# counter.net
KiCad netlist of a schematic drawn in EAGLE
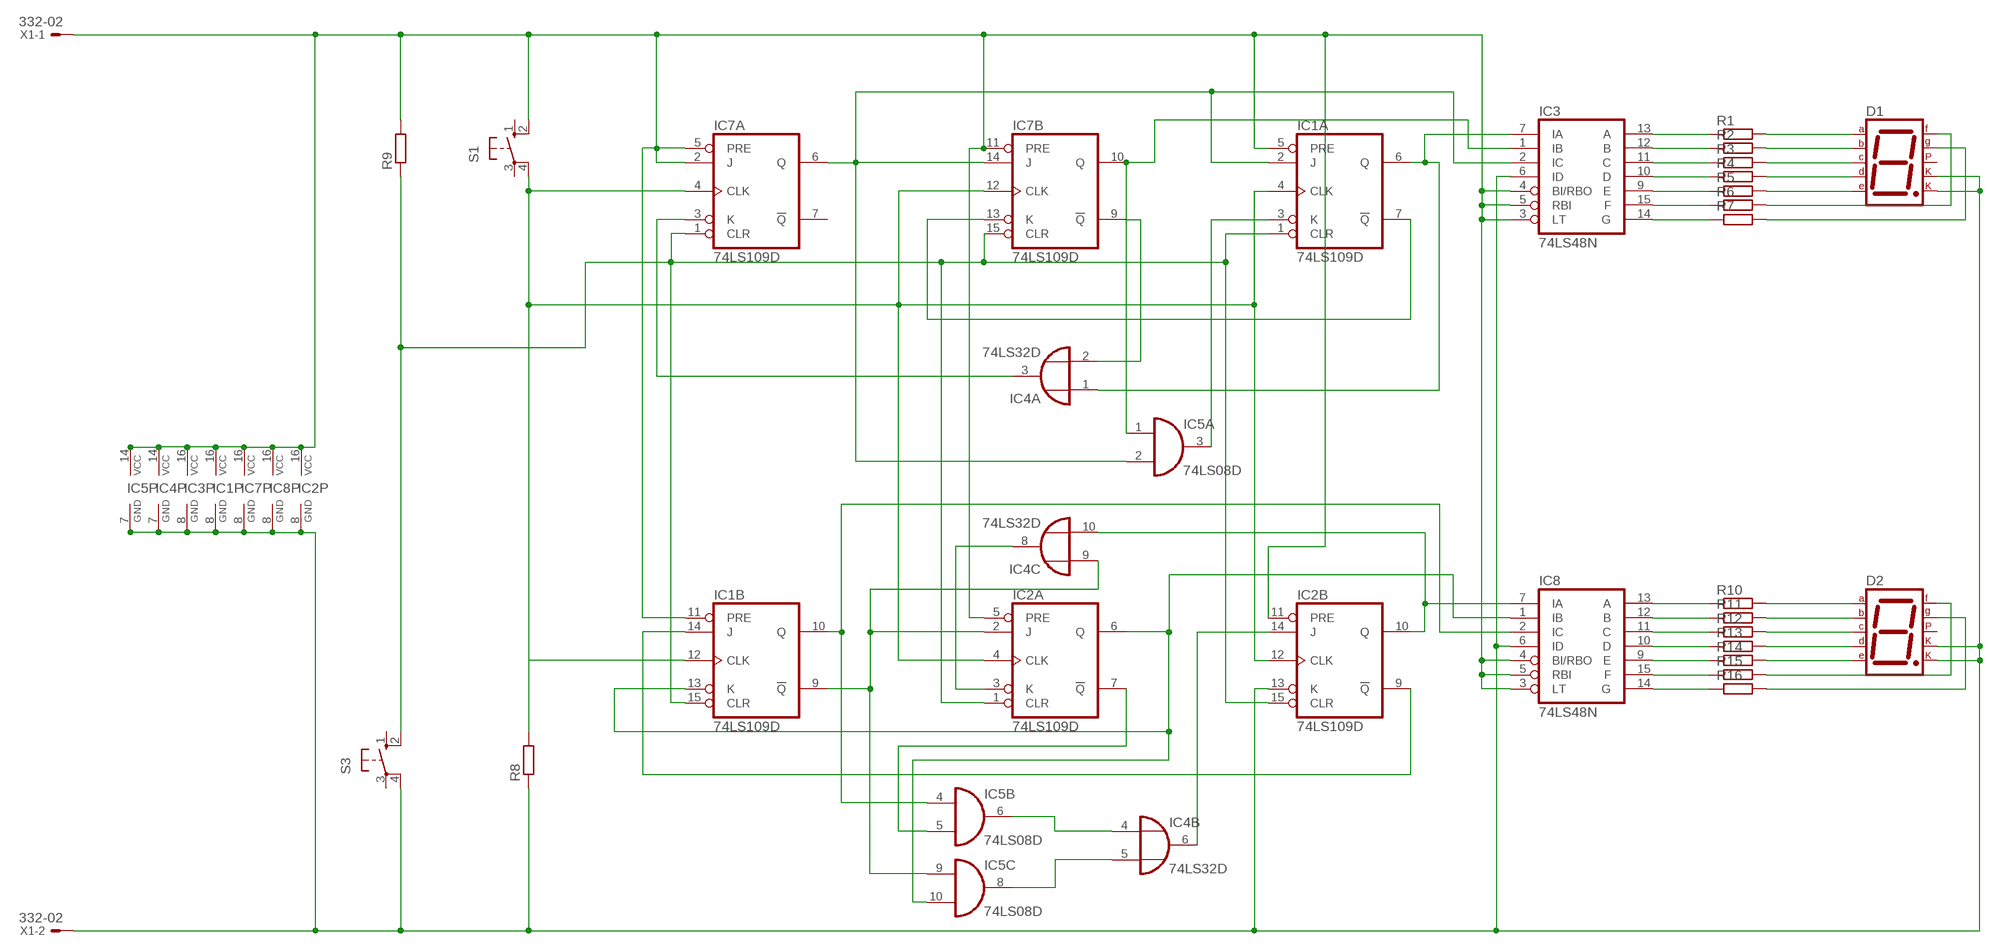
[diagram p0: schematic, sheet 1]

(export (version "E")
  (design (tool "Eeschema 10.0.6"))
  (components
    (comp (ref "D1")
      (value "7SEG-CK")
      (footprint "eagle-import:7SEG-13")
      (libsource (lib "eagle-import") (part "7SEG-CK"))
    )
    (comp (ref "D2")
      (value "7SEG-CK")
      (footprint "eagle-import:7SEG-13")
      (libsource (lib "eagle-import") (part "7SEG-CK"))
    )
    (comp (ref "IC1")
      (value "74LS109D")
      (footprint "eagle-import:SO16")
      (libsource (lib "eagle-import") (part "74109DLS"))
    )
    (comp (ref "IC2")
      (value "74LS109D")
      (footprint "eagle-import:SO16")
      (libsource (lib "eagle-import") (part "74109DLS"))
    )
    (comp (ref "IC3")
      (value "74LS48N")
      (footprint "eagle-import:DIL16")
      (libsource (lib "eagle-import") (part "7448NLS"))
    )
    (comp (ref "IC4")
      (value "74LS32D")
      (footprint "eagle-import:SO14")
      (libsource (lib "eagle-import") (part "7432DLS"))
    )
    (comp (ref "IC5")
      (value "74LS08D")
      (footprint "eagle-import:SO14")
      (libsource (lib "eagle-import") (part "7408DLS"))
    )
    (comp (ref "IC7")
      (value "74LS109D")
      (footprint "eagle-import:SO16")
      (libsource (lib "eagle-import") (part "74109DLS"))
    )
    (comp (ref "IC8")
      (value "74LS48N")
      (footprint "eagle-import:DIL16")
      (libsource (lib "eagle-import") (part "7448NLS"))
    )
    (comp (ref "R1")
      (value "R-EU_M0805")
      (footprint "eagle-import:M0805")
      (libsource (lib "eagle-import") (part "R-EU_M0805"))
    )
    (comp (ref "R2")
      (value "R-EU_M0805")
      (footprint "eagle-import:M0805")
      (libsource (lib "eagle-import") (part "R-EU_M0805"))
    )
    (comp (ref "R3")
      (value "R-EU_M0805")
      (footprint "eagle-import:M0805")
      (libsource (lib "eagle-import") (part "R-EU_M0805"))
    )
    (comp (ref "R4")
      (value "R-EU_M0805")
      (footprint "eagle-import:M0805")
      (libsource (lib "eagle-import") (part "R-EU_M0805"))
    )
    (comp (ref "R5")
      (value "R-EU_M0805")
      (footprint "eagle-import:M0805")
      (libsource (lib "eagle-import") (part "R-EU_M0805"))
    )
    (comp (ref "R6")
      (value "R-EU_M0805")
      (footprint "eagle-import:M0805")
      (libsource (lib "eagle-import") (part "R-EU_M0805"))
    )
    (comp (ref "R7")
      (value "R-EU_M0805")
      (footprint "eagle-import:M0805")
      (libsource (lib "eagle-import") (part "R-EU_M0805"))
    )
    (comp (ref "R8")
      (value "R-EU_M0805")
      (footprint "eagle-import:M0805")
      (libsource (lib "eagle-import") (part "R-EU_M0805"))
    )
    (comp (ref "R9")
      (value "R-EU_M0805")
      (footprint "eagle-import:M0805")
      (libsource (lib "eagle-import") (part "R-EU_M0805"))
    )
    (comp (ref "R10")
      (value "R-EU_M0805")
      (footprint "eagle-import:M0805")
      (libsource (lib "eagle-import") (part "R-EU_M0805"))
    )
    (comp (ref "R11")
      (value "R-EU_M0805")
      (footprint "eagle-import:M0805")
      (libsource (lib "eagle-import") (part "R-EU_M0805"))
    )
    (comp (ref "R12")
      (value "R-EU_M0805")
      (footprint "eagle-import:M0805")
      (libsource (lib "eagle-import") (part "R-EU_M0805"))
    )
    (comp (ref "R13")
      (value "R-EU_M0805")
      (footprint "eagle-import:M0805")
      (libsource (lib "eagle-import") (part "R-EU_M0805"))
    )
    (comp (ref "R14")
      (value "R-EU_M0805")
      (footprint "eagle-import:M0805")
      (libsource (lib "eagle-import") (part "R-EU_M0805"))
    )
    (comp (ref "R15")
      (value "R-EU_M0805")
      (footprint "eagle-import:M0805")
      (libsource (lib "eagle-import") (part "R-EU_M0805"))
    )
    (comp (ref "R16")
      (value "R-EU_M0805")
      (footprint "eagle-import:M0805")
      (libsource (lib "eagle-import") (part "R-EU_M0805"))
    )
    (comp (ref "S1")
      (value "10-XX")
      (footprint "eagle-import:B3F-10XX")
      (fields (field (name "MPN") "B3F-1000"))
      (libsource (lib "eagle-import") (part "10-XX"))
    )
    (comp (ref "S3")
      (value "10-XX")
      (footprint "eagle-import:B3F-10XX")
      (fields (field (name "MPN") "B3F-1000"))
      (libsource (lib "eagle-import") (part "10-XX"))
    )
    (comp (ref "X1")
      (value "332-02")
      (footprint "eagle-import:332-02")
      (libsource (lib "eagle-import") (part "332-02"))
    )
  )
  (nets
    (net (code "1") (name "Net-(D1-A)") (class "Default")
      (node (ref "D1") (pin "7") (pinfunction "A_7") (pintype "passive"))
      (node (ref "R1") (pin "2") (pinfunction "2_2") (pintype "passive"))
    )
    (net (code "2") (name "Net-(D1-B)") (class "Default")
      (node (ref "D1") (pin "6") (pinfunction "B_6") (pintype "passive"))
      (node (ref "R2") (pin "2") (pinfunction "2_2") (pintype "passive"))
    )
    (net (code "3") (name "Net-(D1-C)") (class "Default")
      (node (ref "D1") (pin "4") (pinfunction "C_4") (pintype "passive"))
      (node (ref "R3") (pin "2") (pinfunction "2_2") (pintype "passive"))
    )
    (net (code "4") (name "Net-(D1-CK1)") (class "Default")
      (node (ref "D1") (pin "3") (pinfunction "CK1_3") (pintype "passive"))
      (node (ref "D1") (pin "8") (pinfunction "CK2_8") (pintype "passive"))
      (node (ref "D2") (pin "3") (pinfunction "CK1_3") (pintype "passive"))
      (node (ref "D2") (pin "8") (pinfunction "CK2_8") (pintype "passive"))
      (node (ref "IC1") (pin "8") (pinfunction "GND_8") (pintype "power_in"))
      (node (ref "IC2") (pin "13") (pinfunction "K_13") (pintype "input"))
      (node (ref "IC2") (pin "8") (pinfunction "GND_8") (pintype "power_in"))
      (node (ref "IC3") (pin "6") (pinfunction "ID_6") (pintype "input"))
      (node (ref "IC3") (pin "8") (pinfunction "GND_8") (pintype "power_in"))
      (node (ref "IC4") (pin "7") (pinfunction "GND_7") (pintype "power_in"))
      (node (ref "IC5") (pin "7") (pinfunction "GND_7") (pintype "power_in"))
      (node (ref "IC7") (pin "8") (pinfunction "GND_8") (pintype "power_in"))
      (node (ref "IC8") (pin "6") (pinfunction "ID_6") (pintype "input"))
      (node (ref "IC8") (pin "8") (pinfunction "GND_8") (pintype "power_in"))
      (node (ref "R8") (pin "1") (pinfunction "1_1") (pintype "passive"))
      (node (ref "S3") (pin "4") (pinfunction "P1_4") (pintype "passive"))
      (node (ref "X1") (pin "2") (pinfunction "S_2") (pintype "passive"))
    )
    (net (code "5") (name "Net-(D1-D)") (class "Default")
      (node (ref "D1") (pin "2") (pinfunction "D_2") (pintype "passive"))
      (node (ref "R4") (pin "2") (pinfunction "2_2") (pintype "passive"))
    )
    (net (code "6") (name "Net-(D1-E)") (class "Default")
      (node (ref "D1") (pin "1") (pinfunction "E_1") (pintype "passive"))
      (node (ref "R5") (pin "2") (pinfunction "2_2") (pintype "passive"))
    )
    (net (code "7") (name "Net-(D1-F)") (class "Default")
      (node (ref "D1") (pin "9") (pinfunction "F_9") (pintype "passive"))
      (node (ref "R6") (pin "2") (pinfunction "2_2") (pintype "passive"))
    )
    (net (code "8") (name "Net-(D1-G)") (class "Default")
      (node (ref "D1") (pin "10") (pinfunction "G_10") (pintype "passive"))
      (node (ref "R7") (pin "2") (pinfunction "2_2") (pintype "passive"))
    )
    (net (code "9") (name "Net-(D2-A)") (class "Default")
      (node (ref "D2") (pin "7") (pinfunction "A_7") (pintype "passive"))
      (node (ref "R10") (pin "2") (pinfunction "2_2") (pintype "passive"))
    )
    (net (code "10") (name "Net-(D2-B)") (class "Default")
      (node (ref "D2") (pin "6") (pinfunction "B_6") (pintype "passive"))
      (node (ref "R11") (pin "2") (pinfunction "2_2") (pintype "passive"))
    )
    (net (code "11") (name "Net-(D2-C)") (class "Default")
      (node (ref "D2") (pin "4") (pinfunction "C_4") (pintype "passive"))
      (node (ref "R12") (pin "2") (pinfunction "2_2") (pintype "passive"))
    )
    (net (code "12") (name "Net-(D2-D)") (class "Default")
      (node (ref "D2") (pin "2") (pinfunction "D_2") (pintype "passive"))
      (node (ref "R13") (pin "2") (pinfunction "2_2") (pintype "passive"))
    )
    (net (code "13") (name "Net-(D2-E)") (class "Default")
      (node (ref "D2") (pin "1") (pinfunction "E_1") (pintype "passive"))
      (node (ref "R14") (pin "2") (pinfunction "2_2") (pintype "passive"))
    )
    (net (code "14") (name "Net-(D2-F)") (class "Default")
      (node (ref "D2") (pin "9") (pinfunction "F_9") (pintype "passive"))
      (node (ref "R15") (pin "2") (pinfunction "2_2") (pintype "passive"))
    )
    (net (code "15") (name "Net-(D2-G)") (class "Default")
      (node (ref "D2") (pin "10") (pinfunction "G_10") (pintype "passive"))
      (node (ref "R16") (pin "2") (pinfunction "2_2") (pintype "passive"))
    )
    (net (code "16") (name "Net-(IC1A-CLK)") (class "Default")
      (node (ref "IC1") (pin "12") (pinfunction "CLK_12") (pintype "input"))
      (node (ref "IC1") (pin "4") (pinfunction "CLK_4") (pintype "input"))
      (node (ref "IC2") (pin "12") (pinfunction "CLK_12") (pintype "input"))
      (node (ref "IC2") (pin "4") (pinfunction "CLK_4") (pintype "input"))
      (node (ref "IC7") (pin "12") (pinfunction "CLK_12") (pintype "input"))
      (node (ref "IC7") (pin "4") (pinfunction "CLK_4") (pintype "input"))
      (node (ref "R8") (pin "2") (pinfunction "2_2") (pintype "passive"))
      (node (ref "S1") (pin "4") (pinfunction "P1_4") (pintype "passive"))
    )
    (net (code "17") (name "Net-(IC1A-CLR)") (class "Default")
      (node (ref "IC1") (pin "1") (pinfunction "CLR_1") (pintype "input"))
      (node (ref "IC1") (pin "15") (pinfunction "CLR_15") (pintype "input"))
      (node (ref "IC2") (pin "1") (pinfunction "CLR_1") (pintype "input"))
      (node (ref "IC2") (pin "15") (pinfunction "CLR_15") (pintype "input"))
      (node (ref "IC7") (pin "1") (pinfunction "CLR_1") (pintype "input"))
      (node (ref "IC7") (pin "15") (pinfunction "CLR_15") (pintype "input"))
      (node (ref "R9") (pin "1") (pinfunction "1_1") (pintype "passive"))
      (node (ref "S3") (pin "2") (pinfunction "S1_2") (pintype "passive"))
    )
    (net (code "18") (name "Net-(IC1A-J)") (class "Default")
      (node (ref "IC1") (pin "2") (pinfunction "J_2") (pintype "input"))
      (node (ref "IC3") (pin "2") (pinfunction "IC_2") (pintype "input"))
      (node (ref "IC5") (pin "2") (pinfunction "I1_2") (pintype "input"))
      (node (ref "IC7") (pin "14") (pinfunction "J_14") (pintype "input"))
      (node (ref "IC7") (pin "6") (pinfunction "Q_6") (pintype "output"))
    )
    (net (code "19") (name "Net-(IC1A-K)") (class "Default")
      (node (ref "IC1") (pin "3") (pinfunction "K_3") (pintype "input"))
      (node (ref "IC5") (pin "3") (pinfunction "O_3") (pintype "output"))
    )
    (net (code "20") (name "Net-(IC1A-PRE)") (class "Default")
      (node (ref "IC1") (pin "11") (pinfunction "PRE_11") (pintype "input"))
      (node (ref "IC1") (pin "16") (pinfunction "VCC_16") (pintype "power_in"))
      (node (ref "IC1") (pin "5") (pinfunction "PRE_5") (pintype "input"))
      (node (ref "IC2") (pin "11") (pinfunction "PRE_11") (pintype "input"))
      (node (ref "IC2") (pin "16") (pinfunction "VCC_16") (pintype "power_in"))
      (node (ref "IC2") (pin "5") (pinfunction "PRE_5") (pintype "input"))
      (node (ref "IC3") (pin "16") (pinfunction "VCC_16") (pintype "power_in"))
      (node (ref "IC3") (pin "3") (pinfunction "LT_3") (pintype "input"))
      (node (ref "IC3") (pin "4") (pinfunction "BI/RBO_4") (pintype "input"))
      (node (ref "IC3") (pin "5") (pinfunction "RBI_5") (pintype "input"))
      (node (ref "IC4") (pin "14") (pinfunction "VCC_14") (pintype "power_in"))
      (node (ref "IC5") (pin "14") (pinfunction "VCC_14") (pintype "power_in"))
      (node (ref "IC7") (pin "11") (pinfunction "PRE_11") (pintype "input"))
      (node (ref "IC7") (pin "16") (pinfunction "VCC_16") (pintype "power_in"))
      (node (ref "IC7") (pin "2") (pinfunction "J_2") (pintype "input"))
      (node (ref "IC7") (pin "5") (pinfunction "PRE_5") (pintype "input"))
      (node (ref "IC8") (pin "16") (pinfunction "VCC_16") (pintype "power_in"))
      (node (ref "IC8") (pin "3") (pinfunction "LT_3") (pintype "input"))
      (node (ref "IC8") (pin "4") (pinfunction "BI/RBO_4") (pintype "input"))
      (node (ref "IC8") (pin "5") (pinfunction "RBI_5") (pintype "input"))
      (node (ref "R9") (pin "2") (pinfunction "2_2") (pintype "passive"))
      (node (ref "S1") (pin "2") (pinfunction "S1_2") (pintype "passive"))
      (node (ref "X1") (pin "1") (pinfunction "S_1") (pintype "passive"))
    )
    (net (code "21") (name "Net-(IC1A-Q)") (class "Default")
      (node (ref "IC1") (pin "6") (pinfunction "Q_6") (pintype "output"))
      (node (ref "IC3") (pin "7") (pinfunction "IA_7") (pintype "input"))
      (node (ref "IC4") (pin "1") (pinfunction "I0_1") (pintype "input"))
    )
    (net (code "22") (name "Net-(IC1A-~{Q})") (class "Default")
      (node (ref "IC1") (pin "7") (pinfunction "~{Q}_7") (pintype "output"))
      (node (ref "IC7") (pin "13") (pinfunction "K_13") (pintype "input"))
    )
    (net (code "23") (name "Net-(IC1B-J)") (class "Default")
      (node (ref "IC1") (pin "14") (pinfunction "J_14") (pintype "input"))
      (node (ref "IC2") (pin "9") (pinfunction "~{Q}_9") (pintype "output"))
    )
    (net (code "24") (name "Net-(IC1B-K)") (class "Default")
      (node (ref "IC1") (pin "13") (pinfunction "K_13") (pintype "input"))
      (node (ref "IC2") (pin "6") (pinfunction "Q_6") (pintype "output"))
      (node (ref "IC5") (pin "10") (pinfunction "I1_10") (pintype "input"))
      (node (ref "IC8") (pin "1") (pinfunction "IB_1") (pintype "input"))
    )
    (net (code "25") (name "Net-(IC1B-Q)") (class "Default")
      (node (ref "IC1") (pin "10") (pinfunction "Q_10") (pintype "output"))
      (node (ref "IC5") (pin "4") (pinfunction "I0_4") (pintype "input"))
      (node (ref "IC8") (pin "2") (pinfunction "IC_2") (pintype "input"))
    )
    (net (code "26") (name "Net-(IC1B-~{Q})") (class "Default")
      (node (ref "IC1") (pin "9") (pinfunction "~{Q}_9") (pintype "output"))
      (node (ref "IC2") (pin "2") (pinfunction "J_2") (pintype "input"))
      (node (ref "IC4") (pin "9") (pinfunction "I0_9") (pintype "input"))
      (node (ref "IC5") (pin "9") (pinfunction "I0_9") (pintype "input"))
    )
    (net (code "27") (name "Net-(IC2A-K)") (class "Default")
      (node (ref "IC2") (pin "3") (pinfunction "K_3") (pintype "input"))
      (node (ref "IC4") (pin "8") (pinfunction "O_8") (pintype "output"))
    )
    (net (code "28") (name "Net-(IC2A-~{Q})") (class "Default")
      (node (ref "IC2") (pin "7") (pinfunction "~{Q}_7") (pintype "output"))
      (node (ref "IC5") (pin "5") (pinfunction "I1_5") (pintype "input"))
    )
    (net (code "29") (name "Net-(IC2B-J)") (class "Default")
      (node (ref "IC2") (pin "14") (pinfunction "J_14") (pintype "input"))
      (node (ref "IC4") (pin "6") (pinfunction "O_6") (pintype "output"))
    )
    (net (code "30") (name "Net-(IC2B-Q)") (class "Default")
      (node (ref "IC2") (pin "10") (pinfunction "Q_10") (pintype "output"))
      (node (ref "IC4") (pin "10") (pinfunction "I1_10") (pintype "input"))
      (node (ref "IC8") (pin "7") (pinfunction "IA_7") (pintype "input"))
    )
    (net (code "31") (name "Net-(IC3A-A)") (class "Default")
      (node (ref "IC3") (pin "13") (pinfunction "A_13") (pintype "output"))
      (node (ref "R1") (pin "1") (pinfunction "1_1") (pintype "passive"))
    )
    (net (code "32") (name "Net-(IC3A-B)") (class "Default")
      (node (ref "IC3") (pin "12") (pinfunction "B_12") (pintype "output"))
      (node (ref "R2") (pin "1") (pinfunction "1_1") (pintype "passive"))
    )
    (net (code "33") (name "Net-(IC3A-C)") (class "Default")
      (node (ref "IC3") (pin "11") (pinfunction "C_11") (pintype "output"))
      (node (ref "R3") (pin "1") (pinfunction "1_1") (pintype "passive"))
    )
    (net (code "34") (name "Net-(IC3A-D)") (class "Default")
      (node (ref "IC3") (pin "10") (pinfunction "D_10") (pintype "output"))
      (node (ref "R4") (pin "1") (pinfunction "1_1") (pintype "passive"))
    )
    (net (code "35") (name "Net-(IC3A-E)") (class "Default")
      (node (ref "IC3") (pin "9") (pinfunction "E_9") (pintype "output"))
      (node (ref "R5") (pin "1") (pinfunction "1_1") (pintype "passive"))
    )
    (net (code "36") (name "Net-(IC3A-F)") (class "Default")
      (node (ref "IC3") (pin "15") (pinfunction "F_15") (pintype "output"))
      (node (ref "R6") (pin "1") (pinfunction "1_1") (pintype "passive"))
    )
    (net (code "37") (name "Net-(IC3A-G)") (class "Default")
      (node (ref "IC3") (pin "14") (pinfunction "G_14") (pintype "output"))
      (node (ref "R7") (pin "1") (pinfunction "1_1") (pintype "passive"))
    )
    (net (code "38") (name "Net-(IC3A-IB)") (class "Default")
      (node (ref "IC3") (pin "1") (pinfunction "IB_1") (pintype "input"))
      (node (ref "IC5") (pin "1") (pinfunction "I0_1") (pintype "input"))
      (node (ref "IC7") (pin "10") (pinfunction "Q_10") (pintype "output"))
    )
    (net (code "39") (name "Net-(IC4A-I1)") (class "Default")
      (node (ref "IC4") (pin "2") (pinfunction "I1_2") (pintype "input"))
      (node (ref "IC7") (pin "9") (pinfunction "~{Q}_9") (pintype "output"))
    )
    (net (code "40") (name "Net-(IC4A-O)") (class "Default")
      (node (ref "IC4") (pin "3") (pinfunction "O_3") (pintype "output"))
      (node (ref "IC7") (pin "3") (pinfunction "K_3") (pintype "input"))
    )
    (net (code "41") (name "Net-(IC4B-I0)") (class "Default")
      (node (ref "IC4") (pin "4") (pinfunction "I0_4") (pintype "input"))
      (node (ref "IC5") (pin "6") (pinfunction "O_6") (pintype "output"))
    )
    (net (code "42") (name "Net-(IC4B-I1)") (class "Default")
      (node (ref "IC4") (pin "5") (pinfunction "I1_5") (pintype "input"))
      (node (ref "IC5") (pin "8") (pinfunction "O_8") (pintype "output"))
    )
    (net (code "43") (name "Net-(IC8A-A)") (class "Default")
      (node (ref "IC8") (pin "13") (pinfunction "A_13") (pintype "output"))
      (node (ref "R10") (pin "1") (pinfunction "1_1") (pintype "passive"))
    )
    (net (code "44") (name "Net-(IC8A-B)") (class "Default")
      (node (ref "IC8") (pin "12") (pinfunction "B_12") (pintype "output"))
      (node (ref "R11") (pin "1") (pinfunction "1_1") (pintype "passive"))
    )
    (net (code "45") (name "Net-(IC8A-C)") (class "Default")
      (node (ref "IC8") (pin "11") (pinfunction "C_11") (pintype "output"))
      (node (ref "R12") (pin "1") (pinfunction "1_1") (pintype "passive"))
    )
    (net (code "46") (name "Net-(IC8A-D)") (class "Default")
      (node (ref "IC8") (pin "10") (pinfunction "D_10") (pintype "output"))
      (node (ref "R13") (pin "1") (pinfunction "1_1") (pintype "passive"))
    )
    (net (code "47") (name "Net-(IC8A-E)") (class "Default")
      (node (ref "IC8") (pin "9") (pinfunction "E_9") (pintype "output"))
      (node (ref "R14") (pin "1") (pinfunction "1_1") (pintype "passive"))
    )
    (net (code "48") (name "Net-(IC8A-F)") (class "Default")
      (node (ref "IC8") (pin "15") (pinfunction "F_15") (pintype "output"))
      (node (ref "R15") (pin "1") (pinfunction "1_1") (pintype "passive"))
    )
    (net (code "49") (name "Net-(IC8A-G)") (class "Default")
      (node (ref "IC8") (pin "14") (pinfunction "G_14") (pintype "output"))
      (node (ref "R16") (pin "1") (pinfunction "1_1") (pintype "passive"))
    )
    (net (code "50") (name "unconnected-(D1-DP-Pad5)") (class "Default")
      (node (ref "D1") (pin "5") (pinfunction "DP_5") (pintype "passive"))
    )
    (net (code "51") (name "unconnected-(D2-DP-Pad5)") (class "Default")
      (node (ref "D2") (pin "5") (pinfunction "DP_5") (pintype "passive"))
    )
    (net (code "52") (name "unconnected-(IC7A-~{Q}-Pad7)") (class "Default")
      (node (ref "IC7") (pin "7") (pinfunction "~{Q}_7") (pintype "output"))
    )
    (net (code "53") (name "unconnected-(S1-P-Pad3)") (class "Default")
      (node (ref "S1") (pin "3") (pinfunction "P_3") (pintype "passive"))
    )
    (net (code "54") (name "unconnected-(S1-S-Pad1)") (class "Default")
      (node (ref "S1") (pin "1") (pinfunction "S_1") (pintype "passive"))
    )
    (net (code "55") (name "unconnected-(S3-P-Pad3)") (class "Default")
      (node (ref "S3") (pin "3") (pinfunction "P_3") (pintype "passive"))
    )
    (net (code "56") (name "unconnected-(S3-S-Pad1)") (class "Default")
      (node (ref "S3") (pin "1") (pinfunction "S_1") (pintype "passive"))
    )
  )
)
